# Sheet2.net
KiCad netlist of a schematic drawn in Altium Designer
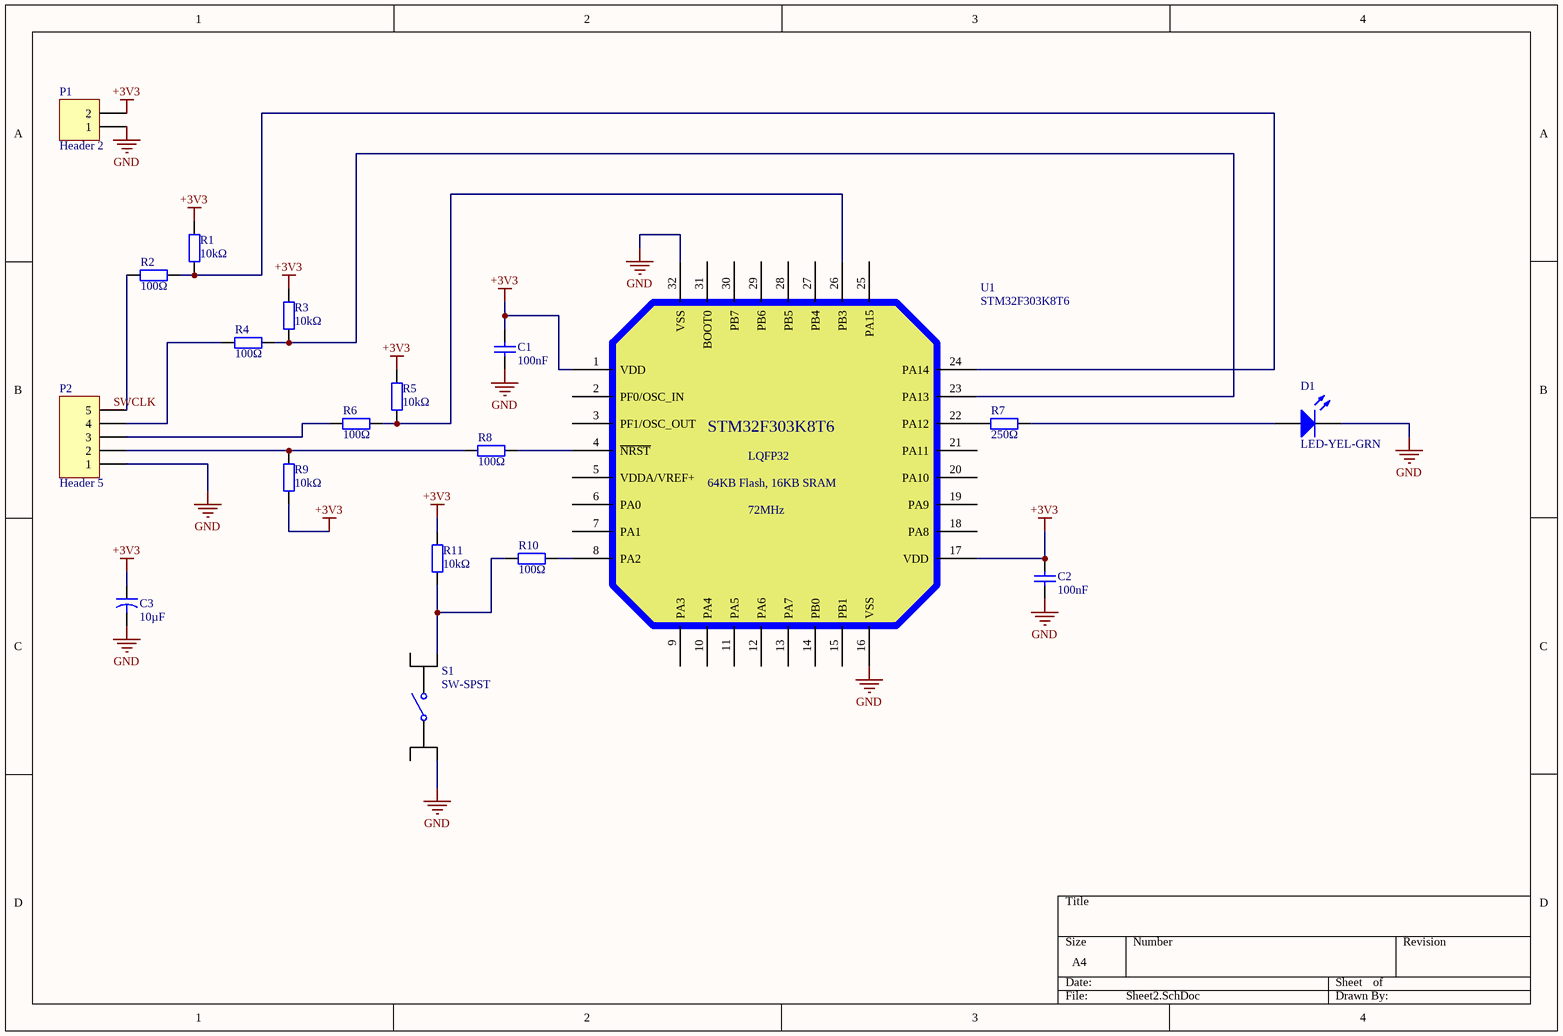
[diagram p0: Sheet2.SchDoc]

(export (version "E")
  (design (tool "Eeschema 10.0.6"))
  (components
    (comp (ref "C1")
      (value "100nF")
      (footprint "capacitor0603nopolar")
      (description "Capacitor")
      (fields (field (name "MANUFACTURER") "WALSIN") (field (name "VOLTAGE") "100V"))
      (libsource (lib "Schlib1") (part "Cap 100nF"))
    )
    (comp (ref "C2")
      (value "100nF")
      (footprint "capacitor0603nopolar")
      (description "Capacitor")
      (fields (field (name "MANUFACTURER") "WALSIN") (field (name "VOLTAGE") "100V"))
      (libsource (lib "Schlib1") (part "Cap 100nF"))
    )
    (comp (ref "C3")
      (value "Cap 10uF")
      (footprint "cappolar_CM1H106M6L006VR")
      (description "Capacitor")
      (fields
        (field (name "CAPACITY") "10µF")
        (field (name "TOLERANCE") "±20%")
        (field (name "MANUFACTURER") "SAMWHA")
      )
      (libsource (lib "Schlib1") (part "Cap 10uF"))
    )
    (comp (ref "D1")
      (value "LED-YEL-GRN")
      (footprint "diode0603")
      (description "Typical INFRARED GaAs LED")
      (fields (field (name "MANUFACTURER") "EVERLIGHT") (field (name "VOLTAGE") "1,7...2,4V"))
      (libsource (lib "Schlib1") (part "LED-YEL-GRN"))
    )
    (comp (ref "P1")
      (value "Header 2")
      (footprint "header2,54")
      (description "Header, 2-Pin")
      (fields (field (name "MANUFACTURER") "TE CONNECTIVITY"))
      (libsource (lib "Schlib1") (part "Header 2"))
    )
    (comp (ref "P2")
      (value "Header 5")
      (footprint "HDR1X5")
      (description "Header, 5-Pin")
      (fields (field (name "PUBLISHER") "Altium Limited"))
      (libsource (lib "Miscellaneous Connectors") (part "Header 5"))
    )
    (comp (ref "R1")
      (value "10kΩ")
      (footprint "resistor0603")
      (description "Resistor")
      (fields (field (name "MANUFACTURER") "ROYAL OHM") (field (name "TOLERANCE") "±1%"))
      (libsource (lib "Schlib1") (part "Resistor 10Kohm"))
    )
    (comp (ref "R2")
      (value "100Ω")
      (footprint "resistor0603")
      (description "Resistor")
      (fields
        (field (name "MANUFACTURER") "WALSIN")
        (field (name "TOLERANCE") "±1%")
        (field (name "RESISTANCE") "100Ω")
      )
      (libsource (lib "Schlib1") (part "Resistor 604ohm"))
    )
    (comp (ref "R3")
      (value "10kΩ")
      (footprint "resistor0603")
      (description "Resistor")
      (fields (field (name "MANUFACTURER") "ROYAL OHM") (field (name "TOLERANCE") "±1%"))
      (libsource (lib "Schlib1") (part "Resistor 10Kohm"))
    )
    (comp (ref "R4")
      (value "100Ω")
      (footprint "resistor0603")
      (description "Resistor")
      (fields
        (field (name "MANUFACTURER") "WALSIN")
        (field (name "TOLERANCE") "±1%")
        (field (name "RESISTANCE") "100Ω")
      )
      (libsource (lib "Schlib1") (part "Resistor 604ohm"))
    )
    (comp (ref "R5")
      (value "10kΩ")
      (footprint "resistor0603")
      (description "Resistor")
      (fields (field (name "MANUFACTURER") "ROYAL OHM") (field (name "TOLERANCE") "±1%"))
      (libsource (lib "Schlib1") (part "Resistor 10Kohm"))
    )
    (comp (ref "R6")
      (value "100Ω")
      (footprint "resistor0603")
      (description "Resistor")
      (fields
        (field (name "MANUFACTURER") "WALSIN")
        (field (name "TOLERANCE") "±1%")
        (field (name "RESISTANCE") "100Ω")
      )
      (libsource (lib "Schlib1") (part "Resistor 604ohm"))
    )
    (comp (ref "R7")
      (value "604Ω")
      (footprint "resistor0603")
      (description "Resistor")
      (fields
        (field (name "MANUFACTURER") "WALSIN")
        (field (name "TOLERANCE") "±1%")
        (field (name "RESISTANCE") "250Ω")
      )
      (libsource (lib "Schlib1") (part "Resistor 604ohm"))
    )
    (comp (ref "R8")
      (value "100Ω")
      (footprint "resistor0603")
      (description "Resistor")
      (fields
        (field (name "MANUFACTURER") "WALSIN")
        (field (name "TOLERANCE") "±1%")
        (field (name "RESISTANCE") "100Ω")
      )
      (libsource (lib "Schlib1") (part "Resistor 604ohm"))
    )
    (comp (ref "R9")
      (value "10kΩ")
      (footprint "resistor0603")
      (description "Resistor")
      (fields (field (name "MANUFACTURER") "ROYAL OHM") (field (name "TOLERANCE") "±1%"))
      (libsource (lib "") (part "Resistor 10Kohm_1"))
    )
    (comp (ref "R10")
      (value "100Ω")
      (footprint "resistor0603")
      (description "Resistor")
      (fields
        (field (name "MANUFACTURER") "WALSIN")
        (field (name "TOLERANCE") "±1%")
        (field (name "RESISTANCE") "100Ω")
      )
      (libsource (lib "Schlib1") (part "Resistor 604ohm"))
    )
    (comp (ref "R11")
      (value "10kΩ")
      (footprint "resistor0603")
      (description "Resistor")
      (fields (field (name "MANUFACTURER") "ROYAL OHM") (field (name "TOLERANCE") "±1%"))
      (libsource (lib "Schlib1") (part "Resistor 10Kohm"))
    )
    (comp (ref "S1")
      (value "SW-SPST")
      (footprint "switch")
      (description "Single-Pole, Single-Throw Switch")
      (fields (field (name "MANUFACTURER") "NKK SWITCHES"))
      (libsource (lib "Schlib1") (part "SW-SPST"))
    )
    (comp (ref "U1")
      (value "STM32F303K8T6")
      (footprint "STM32F303K8T6")
      (description "Microchip")
      (fields (field (name "MANUFACTURER") "STMicroelectronics"))
      (libsource (lib "Schlib1") (part "STM32F303K8T6"))
    )
  )
  (nets
    (net (code "1") (name "+3V3") (class "Default")
      (node (ref "C1") (pin "2") (pinfunction "2_2") (pintype "passive"))
      (node (ref "C2") (pin "2") (pinfunction "2_2") (pintype "passive"))
      (node (ref "C3") (pin "1") (pinfunction "1_1") (pintype "passive"))
      (node (ref "P1") (pin "2") (pinfunction "2_2") (pintype "passive"))
      (node (ref "R1") (pin "2") (pinfunction "2_2") (pintype "passive"))
      (node (ref "R11") (pin "2") (pinfunction "2_2") (pintype "passive"))
      (node (ref "R3") (pin "2") (pinfunction "2_2") (pintype "passive"))
      (node (ref "R5") (pin "2") (pinfunction "2_2") (pintype "passive"))
      (node (ref "R9") (pin "2") (pinfunction "2_2") (pintype "passive"))
      (node (ref "U1") (pin "1") (pinfunction "VDD_1") (pintype "passive"))
      (node (ref "U1") (pin "17") (pinfunction "VDD_17") (pintype "passive"))
    )
    (net (code "3") (name "GND") (class "Default")
      (node (ref "C1") (pin "1") (pinfunction "1_1") (pintype "passive"))
      (node (ref "C2") (pin "1") (pinfunction "1_1") (pintype "passive"))
      (node (ref "C3") (pin "2") (pinfunction "2_2") (pintype "passive"))
      (node (ref "D1") (pin "2") (pinfunction "K_2") (pintype "passive"))
      (node (ref "P1") (pin "1") (pinfunction "1_1") (pintype "passive"))
      (node (ref "P2") (pin "1") (pinfunction "1_1") (pintype "passive"))
      (node (ref "S1") (pin "2") (pinfunction "NO_2") (pintype "passive"))
      (node (ref "U1") (pin "16") (pinfunction "VSS_16") (pintype "passive"))
      (node (ref "U1") (pin "32") (pinfunction "VSS_32") (pintype "passive"))
    )
    (net (code "4") (name "Net-(D1-A)") (class "Default")
      (node (ref "D1") (pin "1") (pinfunction "A_1") (pintype "passive"))
      (node (ref "R7") (pin "2") (pinfunction "2_2") (pintype "passive"))
    )
    (net (code "5") (name "Net-(P2-Pad2)") (class "Default")
      (node (ref "P2") (pin "2") (pinfunction "2_2") (pintype "passive"))
      (node (ref "R8") (pin "1") (pinfunction "1_1") (pintype "passive"))
      (node (ref "R9") (pin "1") (pinfunction "1_1") (pintype "passive"))
    )
    (net (code "6") (name "Net-(P2-Pad3)") (class "Default")
      (node (ref "P2") (pin "3") (pinfunction "3_3") (pintype "passive"))
      (node (ref "R6") (pin "1") (pinfunction "1_1") (pintype "passive"))
    )
    (net (code "7") (name "Net-(P2-Pad4)") (class "Default")
      (node (ref "P2") (pin "4") (pinfunction "4_4") (pintype "passive"))
      (node (ref "R4") (pin "1") (pinfunction "1_1") (pintype "passive"))
    )
    (net (code "8") (name "Net-(P2-Pad5)") (class "Default")
      (node (ref "P2") (pin "5") (pinfunction "5_5") (pintype "passive"))
      (node (ref "R2") (pin "1") (pinfunction "1_1") (pintype "passive"))
    )
    (net (code "9") (name "Net-(R10-Pad1)") (class "Default")
      (node (ref "R10") (pin "1") (pinfunction "1_1") (pintype "passive"))
      (node (ref "R11") (pin "1") (pinfunction "1_1") (pintype "passive"))
      (node (ref "S1") (pin "4") (pinfunction "NO_4") (pintype "passive"))
    )
    (net (code "10") (name "Net-(U1-PA2)") (class "Default")
      (node (ref "R10") (pin "2") (pinfunction "2_2") (pintype "passive"))
      (node (ref "U1") (pin "8") (pinfunction "PA2_8") (pintype "passive"))
    )
    (net (code "11") (name "Net-(U1-PA12)") (class "Default")
      (node (ref "R7") (pin "1") (pinfunction "1_1") (pintype "passive"))
      (node (ref "U1") (pin "22") (pinfunction "PA12_22") (pintype "passive"))
    )
    (net (code "12") (name "Net-(U1-PA13)") (class "Default")
      (node (ref "R3") (pin "1") (pinfunction "1_1") (pintype "passive"))
      (node (ref "R4") (pin "2") (pinfunction "2_2") (pintype "passive"))
      (node (ref "U1") (pin "23") (pinfunction "PA13_23") (pintype "passive"))
    )
    (net (code "13") (name "Net-(U1-PA14)") (class "Default")
      (node (ref "R1") (pin "1") (pinfunction "1_1") (pintype "passive"))
      (node (ref "R2") (pin "2") (pinfunction "2_2") (pintype "passive"))
      (node (ref "U1") (pin "24") (pinfunction "PA14_24") (pintype "passive"))
    )
    (net (code "14") (name "Net-(U1-PB3)") (class "Default")
      (node (ref "R5") (pin "1") (pinfunction "1_1") (pintype "passive"))
      (node (ref "R6") (pin "2") (pinfunction "2_2") (pintype "passive"))
      (node (ref "U1") (pin "26") (pinfunction "PB3_26") (pintype "passive"))
    )
    (net (code "15") (name "Net-(U1-~{NRST})") (class "Default")
      (node (ref "R8") (pin "2") (pinfunction "2_2") (pintype "passive"))
      (node (ref "U1") (pin "4") (pinfunction "~{NRST}_4") (pintype "passive"))
    )
    (net (code "16") (name "unconnected-(S1-NO-Pad1)") (class "Default")
      (node (ref "S1") (pin "1") (pinfunction "NO_1") (pintype "passive"))
    )
    (net (code "17") (name "unconnected-(S1-NO-Pad3)") (class "Default")
      (node (ref "S1") (pin "3") (pinfunction "NO_3") (pintype "passive"))
    )
    (net (code "18") (name "unconnected-(U1-BOOT0-Pad31)") (class "Default")
      (node (ref "U1") (pin "31") (pinfunction "BOOT0_31") (pintype "passive"))
    )
    (net (code "19") (name "unconnected-(U1-PA0-Pad6)") (class "Default")
      (node (ref "U1") (pin "6") (pinfunction "PA0_6") (pintype "passive"))
    )
    (net (code "20") (name "unconnected-(U1-PA1-Pad7)") (class "Default")
      (node (ref "U1") (pin "7") (pinfunction "PA1_7") (pintype "passive"))
    )
    (net (code "21") (name "unconnected-(U1-PA3-Pad9)") (class "Default")
      (node (ref "U1") (pin "9") (pinfunction "PA3_9") (pintype "passive"))
    )
    (net (code "22") (name "unconnected-(U1-PA4-Pad10)") (class "Default")
      (node (ref "U1") (pin "10") (pinfunction "PA4_10") (pintype "passive"))
    )
    (net (code "23") (name "unconnected-(U1-PA5-Pad11)") (class "Default")
      (node (ref "U1") (pin "11") (pinfunction "PA5_11") (pintype "passive"))
    )
    (net (code "24") (name "unconnected-(U1-PA6-Pad12)") (class "Default")
      (node (ref "U1") (pin "12") (pinfunction "PA6_12") (pintype "passive"))
    )
    (net (code "25") (name "unconnected-(U1-PA7-Pad13)") (class "Default")
      (node (ref "U1") (pin "13") (pinfunction "PA7_13") (pintype "passive"))
    )
    (net (code "26") (name "unconnected-(U1-PA8-Pad18)") (class "Default")
      (node (ref "U1") (pin "18") (pinfunction "PA8_18") (pintype "passive"))
    )
    (net (code "27") (name "unconnected-(U1-PA9-Pad19)") (class "Default")
      (node (ref "U1") (pin "19") (pinfunction "PA9_19") (pintype "passive"))
    )
    (net (code "28") (name "unconnected-(U1-PA10-Pad20)") (class "Default")
      (node (ref "U1") (pin "20") (pinfunction "PA10_20") (pintype "passive"))
    )
    (net (code "29") (name "unconnected-(U1-PA11-Pad21)") (class "Default")
      (node (ref "U1") (pin "21") (pinfunction "PA11_21") (pintype "passive"))
    )
    (net (code "30") (name "unconnected-(U1-PA15-Pad25)") (class "Default")
      (node (ref "U1") (pin "25") (pinfunction "PA15_25") (pintype "passive"))
    )
    (net (code "31") (name "unconnected-(U1-PB0-Pad14)") (class "Default")
      (node (ref "U1") (pin "14") (pinfunction "PB0_14") (pintype "passive"))
    )
    (net (code "32") (name "unconnected-(U1-PB1-Pad15)") (class "Default")
      (node (ref "U1") (pin "15") (pinfunction "PB1_15") (pintype "passive"))
    )
    (net (code "33") (name "unconnected-(U1-PB4-Pad27)") (class "Default")
      (node (ref "U1") (pin "27") (pinfunction "PB4_27") (pintype "passive"))
    )
    (net (code "34") (name "unconnected-(U1-PB5-Pad28)") (class "Default")
      (node (ref "U1") (pin "28") (pinfunction "PB5_28") (pintype "passive"))
    )
    (net (code "35") (name "unconnected-(U1-PB6-Pad29)") (class "Default")
      (node (ref "U1") (pin "29") (pinfunction "PB6_29") (pintype "passive"))
    )
    (net (code "36") (name "unconnected-(U1-PB7-Pad30)") (class "Default")
      (node (ref "U1") (pin "30") (pinfunction "PB7_30") (pintype "passive"))
    )
    (net (code "37") (name "unconnected-(U1-PF0{slash}OSC_IN-Pad2)") (class "Default")
      (node (ref "U1") (pin "2") (pinfunction "PF0/OSC_IN_2") (pintype "passive"))
    )
    (net (code "38") (name "unconnected-(U1-PF1{slash}OSC_OUT-Pad3)") (class "Default")
      (node (ref "U1") (pin "3") (pinfunction "PF1/OSC_OUT_3") (pintype "passive"))
    )
    (net (code "39") (name "unconnected-(U1-VDDA{slash}VREF+-Pad5)") (class "Default")
      (node (ref "U1") (pin "5") (pinfunction "VDDA/VREF+_5") (pintype "passive"))
    )
  )
)
